# MCU.net
KiCad netlist of a schematic drawn in Altium Designer
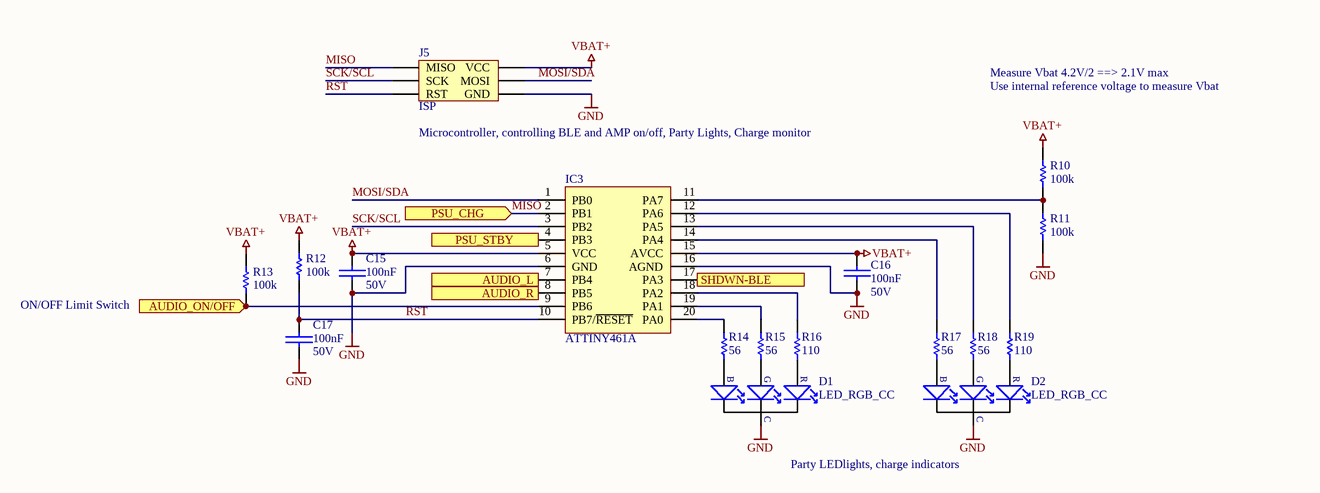
[diagram p0: MCU.SchDoc]

(export (version "E")
  (design (tool "Eeschema 10.0.6"))
  (components
    (comp (ref "C15")
      (value "100nF")
      (footprint "TH5.08")
      (description "CAP CER TH 100nF X7R 50V")
      (fields
        (field (name "MANUFACTURER") "FH")
        (field (name "TOLERANCE") "10%")
        (field (name "VOLTAGE") "50V")
      )
      (libsource (lib "js-altium-library") (part "cap_non_pol"))
    )
    (comp (ref "C16")
      (value "100nF")
      (footprint "TH5.08")
      (description "CAP CER TH 100nF X7R 50V")
      (fields
        (field (name "MANUFACTURER") "FH")
        (field (name "TOLERANCE") "10%")
        (field (name "VOLTAGE") "50V")
      )
      (libsource (lib "js-altium-library") (part "cap_non_pol"))
    )
    (comp (ref "C17")
      (value "100nF")
      (footprint "TH5.08")
      (description "CAP CER TH 100nF X7R 50V")
      (fields
        (field (name "MANUFACTURER") "FH")
        (field (name "TOLERANCE") "10%")
        (field (name "VOLTAGE") "50V")
      )
      (libsource (lib "js-altium-library") (part "cap_non_pol"))
    )
    (comp (ref "D1")
      (value "LED_RGB_CC")
      (footprint "5MM-RGB-CC")
      (description "LED (RGB)")
      (fields (field (name "MANUFACTURER") "TOGIALED"))
      (libsource (lib "js-altium-library") (part "LED_RGB_CC"))
    )
    (comp (ref "D2")
      (value "LED_RGB_CC")
      (footprint "5MM-RGB-CC")
      (description "LED (RGB)")
      (fields (field (name "MANUFACTURER") "TOGIALED"))
      (libsource (lib "js-altium-library") (part "LED_RGB_CC"))
    )
    (comp (ref "IC3")
      (value "ATTINY461A")
      (footprint "PDIP-20")
      (description "IC MCU 8BIT 4KB FLASH 20DIP")
      (fields (field (name "MANUFACTURER") "Microchip Technology"))
      (libsource (lib "js-altium-library") (part "ATTINY461A"))
    )
    (comp (ref "J5")
      (value "ISP")
      (footprint "ISP_COMPACT")
      (description "CONN 6 PIN SOLDER PADS FOR ISP")
      (libsource (lib "js-altium-library") (part "ISP"))
    )
    (comp (ref "R10")
      (value "100k")
      (footprint "TH6.3")
      (description "RES TH 100k OHM 5% 1/4W")
      (fields (field (name "MANUFACTURER") "VO") (field (name "TOLERANCE") "5%"))
      (libsource (lib "js-altium-library") (part "resistor"))
    )
    (comp (ref "R11")
      (value "100k")
      (footprint "TH6.3")
      (description "RES TH 100k OHM 5% 1/4W")
      (fields (field (name "MANUFACTURER") "VO") (field (name "TOLERANCE") "5%"))
      (libsource (lib "js-altium-library") (part "resistor"))
    )
    (comp (ref "R12")
      (value "100k")
      (footprint "TH6.3")
      (description "RES TH 100k OHM 5% 1/4W")
      (fields (field (name "MANUFACTURER") "VO") (field (name "TOLERANCE") "5%"))
      (libsource (lib "js-altium-library") (part "resistor"))
    )
    (comp (ref "R13")
      (value "100k")
      (footprint "TH6.3")
      (description "RES TH 100k OHM 5% 1/4W")
      (fields (field (name "MANUFACTURER") "VO") (field (name "TOLERANCE") "5%"))
      (libsource (lib "js-altium-library") (part "resistor"))
    )
    (comp (ref "R14")
      (value "56")
      (footprint "TH6.3")
      (description "RES TH 56 OHM 5% 1/8W")
      (fields (field (name "MANUFACTURER") "VO") (field (name "TOLERANCE") "5%"))
      (libsource (lib "js-altium-library") (part "resistor"))
    )
    (comp (ref "R15")
      (value "56")
      (footprint "TH6.3")
      (description "RES TH 56 OHM 5% 1/8W")
      (fields (field (name "MANUFACTURER") "VO") (field (name "TOLERANCE") "5%"))
      (libsource (lib "js-altium-library") (part "resistor"))
    )
    (comp (ref "R16")
      (value "110")
      (footprint "TH6.3")
      (description "RES TH 110 OHM 1% 1/8W")
      (fields (field (name "MANUFACTURER") "Huaxing Mechanical-Elec.") (field (name "TOLERANCE") "1%"))
      (libsource (lib "js-altium-library") (part "resistor"))
    )
    (comp (ref "R17")
      (value "56")
      (footprint "TH6.3")
      (description "RES TH 56 OHM 5% 1/8W")
      (fields (field (name "MANUFACTURER") "VO") (field (name "TOLERANCE") "5%"))
      (libsource (lib "js-altium-library") (part "resistor"))
    )
    (comp (ref "R18")
      (value "56")
      (footprint "TH6.3")
      (description "RES TH 56 OHM 5% 1/8W")
      (fields (field (name "MANUFACTURER") "VO") (field (name "TOLERANCE") "5%"))
      (libsource (lib "js-altium-library") (part "resistor"))
    )
    (comp (ref "R19")
      (value "110")
      (footprint "TH6.3")
      (description "RES TH 110 OHM 1% 1/8W")
      (fields (field (name "MANUFACTURER") "Huaxing Mechanical-Elec.") (field (name "TOLERANCE") "1%"))
      (libsource (lib "js-altium-library") (part "resistor"))
    )
  )
  (nets
    (net (code "1") (name "/AUDIO_L") (class "Default")
      (node (ref "IC3") (pin "7") (pinfunction "PB4_7") (pintype "passive"))
    )
    (net (code "2") (name "/AUDIO_ON{slash}OFF") (class "Default")
      (node (ref "IC3") (pin "9") (pinfunction "PB6_9") (pintype "passive"))
      (node (ref "R13") (pin "1") (pinfunction "1_1") (pintype "passive"))
    )
    (net (code "3") (name "/AUDIO_R") (class "Default")
      (node (ref "IC3") (pin "8") (pinfunction "PB5_8") (pintype "passive"))
    )
    (net (code "4") (name "/MISO") (class "Default")
      (node (ref "IC3") (pin "2") (pinfunction "PB1_2") (pintype "passive"))
      (node (ref "J5") (pin "MISO") (pinfunction "MISO_MISO") (pintype "passive"))
    )
    (net (code "5") (name "/MOSI{slash}SDA") (class "Default")
      (node (ref "IC3") (pin "1") (pinfunction "PB0_1") (pintype "passive"))
      (node (ref "J5") (pin "MOSI") (pinfunction "MOSI_MOSI") (pintype "passive"))
    )
    (net (code "6") (name "/PSU_STBY") (class "Default")
      (node (ref "IC3") (pin "4") (pinfunction "PB3_4") (pintype "passive"))
    )
    (net (code "7") (name "/RST") (class "Default")
      (node (ref "C17") (pin "1") (pinfunction "1_1") (pintype "passive"))
      (node (ref "IC3") (pin "10") (pinfunction "PB7/~{RESET}_10") (pintype "passive"))
      (node (ref "J5") (pin "RST") (pinfunction "RST_RST") (pintype "passive"))
      (node (ref "R12") (pin "1") (pinfunction "1_1") (pintype "passive"))
    )
    (net (code "8") (name "/SCK{slash}SCL") (class "Default")
      (node (ref "IC3") (pin "3") (pinfunction "PB2_3") (pintype "passive"))
      (node (ref "J5") (pin "SCK") (pinfunction "SCK_SCK") (pintype "passive"))
    )
    (net (code "9") (name "/SHDWN-BLE") (class "Default")
      (node (ref "IC3") (pin "17") (pinfunction "PA3_17") (pintype "passive"))
    )
    (net (code "10") (name "GND") (class "Default")
      (node (ref "C15") (pin "2") (pinfunction "2_2") (pintype "passive"))
      (node (ref "C16") (pin "2") (pinfunction "2_2") (pintype "passive"))
      (node (ref "C17") (pin "2") (pinfunction "2_2") (pintype "passive"))
      (node (ref "D1") (pin "C") (pinfunction "C_C") (pintype "passive"))
      (node (ref "D2") (pin "C") (pinfunction "C_C") (pintype "passive"))
      (node (ref "IC3") (pin "16") (pinfunction "AGND_16") (pintype "passive"))
      (node (ref "IC3") (pin "6") (pinfunction "GND_6") (pintype "passive"))
      (node (ref "J5") (pin "GND") (pinfunction "GND_GND") (pintype "passive"))
      (node (ref "R11") (pin "1") (pinfunction "1_1") (pintype "passive"))
    )
    (net (code "11") (name "Net-(D1-PadB)") (class "Default")
      (node (ref "D1") (pin "B") (pinfunction "B_B") (pintype "passive"))
      (node (ref "R14") (pin "2") (pinfunction "2_2") (pintype "passive"))
    )
    (net (code "12") (name "Net-(D1-PadG)") (class "Default")
      (node (ref "D1") (pin "G") (pinfunction "G_G") (pintype "passive"))
      (node (ref "R15") (pin "2") (pinfunction "2_2") (pintype "passive"))
    )
    (net (code "13") (name "Net-(D1-PadR)") (class "Default")
      (node (ref "D1") (pin "R") (pinfunction "R_R") (pintype "passive"))
      (node (ref "R16") (pin "2") (pinfunction "2_2") (pintype "passive"))
    )
    (net (code "14") (name "Net-(D2-PadB)") (class "Default")
      (node (ref "D2") (pin "B") (pinfunction "B_B") (pintype "passive"))
      (node (ref "R17") (pin "2") (pinfunction "2_2") (pintype "passive"))
    )
    (net (code "15") (name "Net-(D2-PadG)") (class "Default")
      (node (ref "D2") (pin "G") (pinfunction "G_G") (pintype "passive"))
      (node (ref "R18") (pin "2") (pinfunction "2_2") (pintype "passive"))
    )
    (net (code "16") (name "Net-(D2-PadR)") (class "Default")
      (node (ref "D2") (pin "R") (pinfunction "R_R") (pintype "passive"))
      (node (ref "R19") (pin "2") (pinfunction "2_2") (pintype "passive"))
    )
    (net (code "17") (name "Net-(IC3-PA0)") (class "Default")
      (node (ref "IC3") (pin "20") (pinfunction "PA0_20") (pintype "passive"))
      (node (ref "R14") (pin "1") (pinfunction "1_1") (pintype "passive"))
    )
    (net (code "18") (name "Net-(IC3-PA1)") (class "Default")
      (node (ref "IC3") (pin "19") (pinfunction "PA1_19") (pintype "passive"))
      (node (ref "R15") (pin "1") (pinfunction "1_1") (pintype "passive"))
    )
    (net (code "19") (name "Net-(IC3-PA2)") (class "Default")
      (node (ref "IC3") (pin "18") (pinfunction "PA2_18") (pintype "passive"))
      (node (ref "R16") (pin "1") (pinfunction "1_1") (pintype "passive"))
    )
    (net (code "20") (name "Net-(IC3-PA4)") (class "Default")
      (node (ref "IC3") (pin "14") (pinfunction "PA4_14") (pintype "passive"))
      (node (ref "R17") (pin "1") (pinfunction "1_1") (pintype "passive"))
    )
    (net (code "21") (name "Net-(IC3-PA5)") (class "Default")
      (node (ref "IC3") (pin "13") (pinfunction "PA5_13") (pintype "passive"))
      (node (ref "R18") (pin "1") (pinfunction "1_1") (pintype "passive"))
    )
    (net (code "22") (name "Net-(IC3-PA6)") (class "Default")
      (node (ref "IC3") (pin "12") (pinfunction "PA6_12") (pintype "passive"))
      (node (ref "R19") (pin "1") (pinfunction "1_1") (pintype "passive"))
    )
    (net (code "23") (name "Net-(IC3-PA7)") (class "Default")
      (node (ref "IC3") (pin "11") (pinfunction "PA7_11") (pintype "passive"))
      (node (ref "R10") (pin "1") (pinfunction "1_1") (pintype "passive"))
      (node (ref "R11") (pin "2") (pinfunction "2_2") (pintype "passive"))
    )
    (net (code "24") (name "VBAT+") (class "Default")
      (node (ref "C15") (pin "1") (pinfunction "1_1") (pintype "passive"))
      (node (ref "C16") (pin "1") (pinfunction "1_1") (pintype "passive"))
      (node (ref "IC3") (pin "15") (pinfunction "AVCC_15") (pintype "passive"))
      (node (ref "IC3") (pin "5") (pinfunction "VCC_5") (pintype "passive"))
      (node (ref "J5") (pin "VCC") (pinfunction "VCC_VCC") (pintype "passive"))
      (node (ref "R10") (pin "2") (pinfunction "2_2") (pintype "passive"))
      (node (ref "R12") (pin "2") (pinfunction "2_2") (pintype "passive"))
      (node (ref "R13") (pin "2") (pinfunction "2_2") (pintype "passive"))
    )
  )
)
